# PowerSupply.net
KiCad netlist of a schematic drawn in Altium Designer
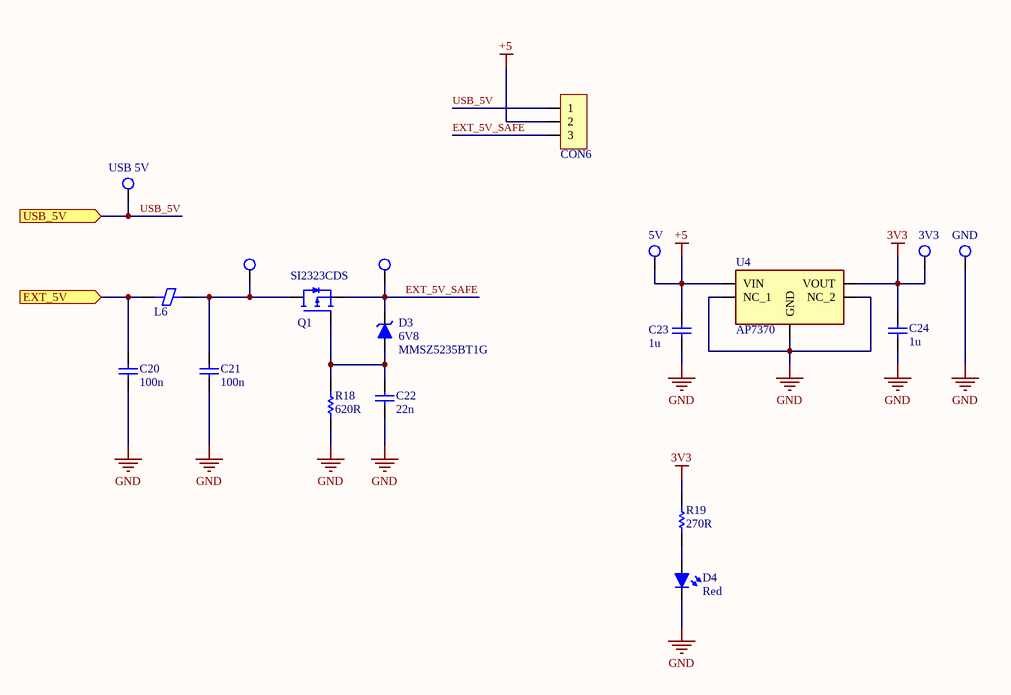
[diagram p0: PowerSupply.SchDoc]

(export (version "E")
  (design (tool "Eeschema 10.0.6"))
  (components
    (comp (ref "C20")
      (value "100n")
      (footprint "Cap_0402_MD_outline")
      (description "Capacitor")
      (fields (field (name "MPN") "GRM155R71H103MA88"))
      (libsource (lib "LibPassive") (part "Capacitor"))
    )
    (comp (ref "C21")
      (value "100n")
      (footprint "Cap_0402_MD_outline")
      (description "Capacitor")
      (fields (field (name "MPN") "GRM155R71H103MA88"))
      (libsource (lib "LibPassive") (part "Capacitor"))
    )
    (comp (ref "C22")
      (value "22n")
      (footprint "Cap_0603_MD_outline")
      (description "Capacitor")
      (fields (field (name "MPN") "GRM188R72A223KAC4D"))
      (libsource (lib "LibPassive") (part "Capacitor"))
    )
    (comp (ref "C23")
      (value "1u")
      (footprint "Cap_0805_MD_outline")
      (description "Capacitor")
      (fields (field (name "MPN") "GRM219R7YA105KA12"))
      (libsource (lib "LibPassive") (part "Capacitor"))
    )
    (comp (ref "C24")
      (value "1u")
      (footprint "Cap_0805_MD_outline")
      (description "Capacitor")
      (fields (field (name "MPN") "GRM219R7YA105KA12"))
      (libsource (lib "LibPassive") (part "Capacitor"))
    )
    (comp (ref "CON6")
      (value "Header 3")
      (footprint "HDR_1X3_2.54")
      (description "Header, 3-Pin")
      (fields (field (name "MPN") "G800LR305018EU"))
      (libsource (lib "Library") (part "Header 3"))
    )
    (comp (ref "D3")
      (value "MMSZ5235BT1G")
      (footprint "SOD3716X135N")
      (description "Zener Diode")
      (fields (field (name "ZENER VOLATGE") "6V8"))
      (libsource (lib "Library") (part "MMSZ5240BT1G"))
    )
    (comp (ref "D4")
      (value "Red")
      (footprint "LED_0805_OUTLINE")
      (description "LED")
      (fields (field (name "MPN") "599-0110-007F"))
      (libsource (lib "Library") (part "LED"))
    )
    (comp (ref "L6")
      (value "~")
      (footprint "Bead_0402_MD_Outline")
      (description "Ferrite bead")
      (fields (field (name "MPN") "BLM15PX601SN1"))
      (libsource (lib "LibPassive") (part "Bead"))
    )
    (comp (ref "Q1")
      (value "SI2323CDS")
      (footprint "SOT95P237X112-3N")
      (description "P-MOSFET")
      (fields (field (name "MPN") "SI2323CDS-T1-GE3"))
      (libsource (lib "Library") (part "SI2323CDS"))
    )
    (comp (ref "R18")
      (value "620R")
      (footprint "Res_0603_MD_outline")
      (description "Resistor")
      (fields (field (name "MPN") "CRCW0603620RFKEAC"))
      (libsource (lib "LibPassive") (part "Resistor"))
    )
    (comp (ref "R19")
      (value "270R")
      (footprint "Res_0805_MD_outline")
      (description "Resistor")
      (fields (field (name "MPN") "RCS0805270RFKEA"))
      (libsource (lib "LibPassive") (part "Resistor"))
    )
    (comp (ref "TP16")
      (value "USB 5V")
      (footprint "TP_SQ40")
      (description "Test point")
      (libsource (lib "Library") (part "TestPoint"))
    )
    (comp (ref "TP17")
      (value "*")
      (footprint "TP_SQ40")
      (description "Test point")
      (libsource (lib "Library") (part "TestPoint"))
    )
    (comp (ref "TP18")
      (value "*")
      (footprint "TP_SQ40")
      (description "Test point")
      (libsource (lib "Library") (part "TestPoint"))
    )
    (comp (ref "TP19")
      (value "5V")
      (footprint "TP_SQ40")
      (description "Test point")
      (libsource (lib "Library") (part "TestPoint"))
    )
    (comp (ref "TP20")
      (value "3V3")
      (footprint "TP_SQ40")
      (description "Test point")
      (libsource (lib "Library") (part "TestPoint"))
    )
    (comp (ref "TP21")
      (value "GND")
      (footprint "TP_SQ40")
      (description "Test point")
      (libsource (lib "Library") (part "TestPoint"))
    )
    (comp (ref "U4")
      (value "AP7370")
      (footprint "SOT95P285X140-5N")
      (description "Volatge Regulator 3V3")
      (fields
        (field (name "MOUSER PART NUMBER") "621-AP7370-33WW-7")
        (field (name "ARROW PART NUMBER") "AP7370-33WW-7")
      )
      (libsource (lib "Library") (part "AP7370-33WW-7"))
    )
  )
  (nets
    (net (code "1") (name "+5") (class "Default")
      (node (ref "C23") (pin "2") (pinfunction "2_2") (pintype "passive"))
      (node (ref "CON6") (pin "2") (pinfunction "2_2") (pintype "passive"))
      (node (ref "TP19") (pin "1") (pintype "passive"))
      (node (ref "U4") (pin "1") (pinfunction "VIN_1") (pintype "passive"))
    )
    (net (code "2") (name "/EXT_5V") (class "Default")
      (node (ref "C20") (pin "1") (pinfunction "1_1") (pintype "passive"))
      (node (ref "L6") (pin "1") (pintype "passive"))
    )
    (net (code "3") (name "/EXT_5V_SAFE") (class "Default")
      (node (ref "CON6") (pin "3") (pinfunction "3_3") (pintype "passive"))
      (node (ref "D3") (pin "1") (pinfunction "K_1") (pintype "passive"))
      (node (ref "Q1") (pin "2") (pinfunction "S_2") (pintype "passive"))
      (node (ref "TP18") (pin "1") (pintype "passive"))
    )
    (net (code "4") (name "/USB_5V") (class "Default")
      (node (ref "CON6") (pin "1") (pinfunction "1_1") (pintype "passive"))
      (node (ref "TP16") (pin "1") (pintype "passive"))
    )
    (net (code "5") (name "3V3") (class "Default")
      (node (ref "C24") (pin "2") (pinfunction "2_2") (pintype "passive"))
      (node (ref "R19") (pin "2") (pinfunction "2_2") (pintype "passive"))
      (node (ref "TP20") (pin "1") (pintype "passive"))
      (node (ref "U4") (pin "3") (pinfunction "VOUT_3") (pintype "passive"))
    )
    (net (code "6") (name "GND") (class "Default")
      (node (ref "C20") (pin "2") (pinfunction "2_2") (pintype "passive"))
      (node (ref "C21") (pin "1") (pinfunction "1_1") (pintype "passive"))
      (node (ref "C22") (pin "1") (pinfunction "1_1") (pintype "passive"))
      (node (ref "C23") (pin "1") (pinfunction "1_1") (pintype "passive"))
      (node (ref "C24") (pin "1") (pinfunction "1_1") (pintype "passive"))
      (node (ref "D4") (pin "K") (pinfunction "K_K") (pintype "passive"))
      (node (ref "R18") (pin "1") (pinfunction "1_1") (pintype "passive"))
      (node (ref "TP21") (pin "1") (pintype "passive"))
      (node (ref "U4") (pin "2") (pinfunction "GND_2") (pintype "passive"))
      (node (ref "U4") (pin "4") (pinfunction "NC_1_4") (pintype "passive"))
      (node (ref "U4") (pin "5") (pinfunction "NC_2_5") (pintype "passive"))
    )
    (net (code "7") (name "Net-(D3-A)") (class "Default")
      (node (ref "C22") (pin "2") (pinfunction "2_2") (pintype "passive"))
      (node (ref "D3") (pin "2") (pinfunction "A_2") (pintype "passive"))
      (node (ref "Q1") (pin "1") (pinfunction "G_1") (pintype "passive"))
      (node (ref "R18") (pin "2") (pinfunction "2_2") (pintype "passive"))
    )
    (net (code "8") (name "Net-(D4-PadA)") (class "Default")
      (node (ref "D4") (pin "A") (pinfunction "A_A") (pintype "passive"))
      (node (ref "R19") (pin "1") (pinfunction "1_1") (pintype "passive"))
    )
    (net (code "9") (name "Net-(Q1-D)") (class "Default")
      (node (ref "C21") (pin "2") (pinfunction "2_2") (pintype "passive"))
      (node (ref "L6") (pin "2") (pintype "passive"))
      (node (ref "Q1") (pin "3") (pinfunction "D_3") (pintype "passive"))
      (node (ref "TP17") (pin "1") (pintype "passive"))
    )
  )
)
